# TempHumiditySensorBoard.net
KiCad netlist of a schematic drawn in EAGLE
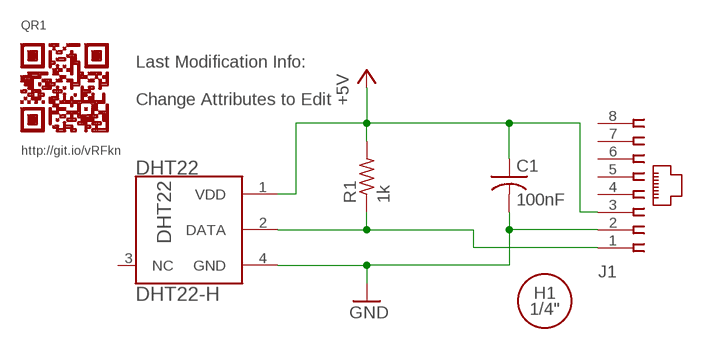
[diagram p0: schematic, sheet 1]

(export (version "E")
  (design (tool "Eeschema 10.0.6"))
  (components
    (comp (ref "C1")
      (value "100nF")
      (footprint "eagle-import:C1206")
      (fields (field (name "PARTNO") "CL31B104JBCNNNC"))
      (libsource (lib "eagle-import") (part "C-USC1206"))
    )
    (comp (ref "DHT22")
      (value "DHT22-H")
      (footprint "eagle-import:DHT22-H")
      (fields (field (name "PARTNO") "385"))
      (libsource (lib "eagle-import") (part "DHT22-H"))
    )
    (comp (ref "H1")
      (value "MOUNT-HOLE-1/4\"-FREE")
      (footprint "eagle-import:MOUNT-HOLE-1_4_-FREE")
      (libsource (lib "eagle-import") (part "MOUNT-HOLE-1/4{dblquote}-FREE"))
    )
    (comp (ref "J1")
      (value "555164-1")
      (footprint "eagle-import:555164-1")
      (libsource (lib "eagle-import") (part "555164-1"))
    )
    (comp (ref "QR1")
      (value "QR-HTTP://GIT.IO/VRFKN")
      (footprint "eagle-import:QR-HTTP___GIT.IO_VRFKN")
      (libsource (lib "eagle-import") (part "QR-HTTP{colon}//GIT.IO/VRFKN"))
    )
    (comp (ref "R1")
      (value "1k")
      (footprint "eagle-import:R1206")
      (fields (field (name "PARTNO") "ERJ-8ENF2001V"))
      (libsource (lib "eagle-import") (part "R-US_R1206"))
    )
    (comp (ref "U$2")
      (value "INFOROW")
      (footprint "eagle-import:INIT_DATE_LINE")
      (fields (field (name "MODAUTH") "ZSS") (field (name "MODDATE") "2015-12-09"))
      (libsource (lib "eagle-import") (part "INFOROW"))
    )
  )
  (nets
    (net (code "1") (name "+5V") (class "Default")
      (node (ref "C1") (pin "1") (pinfunction "1_1") (pintype "passive"))
      (node (ref "DHT22") (pin "1") (pinfunction "VDD_1") (pintype "power_in"))
      (node (ref "J1") (pin "3") (pinfunction "3_3") (pintype "passive"))
      (node (ref "R1") (pin "2") (pinfunction "2_2") (pintype "passive"))
    )
    (net (code "2") (name "GND") (class "Default")
      (node (ref "C1") (pin "2") (pinfunction "2_2") (pintype "passive"))
      (node (ref "DHT22") (pin "4") (pinfunction "GND_4") (pintype "power_in"))
      (node (ref "J1") (pin "2") (pinfunction "2_2") (pintype "passive"))
    )
    (net (code "3") (name "Net-(DHT22-DATA)") (class "Default")
      (node (ref "DHT22") (pin "2") (pinfunction "DATA_2") (pintype "bidirectional"))
      (node (ref "J1") (pin "1") (pinfunction "1_1") (pintype "passive"))
      (node (ref "R1") (pin "1") (pinfunction "1_1") (pintype "passive"))
    )
    (net (code "4") (name "unconnected-(DHT22-NC-Pad3)") (class "Default")
      (node (ref "DHT22") (pin "3") (pinfunction "NC_3") (pintype "bidirectional"))
    )
    (net (code "5") (name "unconnected-(J1-Pad4)") (class "Default")
      (node (ref "J1") (pin "4") (pinfunction "4_4") (pintype "passive"))
    )
    (net (code "6") (name "unconnected-(J1-Pad5)") (class "Default")
      (node (ref "J1") (pin "5") (pinfunction "5_5") (pintype "passive"))
    )
    (net (code "7") (name "unconnected-(J1-Pad6)") (class "Default")
      (node (ref "J1") (pin "6") (pinfunction "6_6") (pintype "passive"))
    )
    (net (code "8") (name "unconnected-(J1-Pad7)") (class "Default")
      (node (ref "J1") (pin "7") (pinfunction "7_7") (pintype "passive"))
    )
    (net (code "9") (name "unconnected-(J1-Pad8)") (class "Default")
      (node (ref "J1") (pin "8") (pinfunction "8_8") (pintype "passive"))
    )
  )
)
